# Led_Control.net
KiCad netlist of a schematic drawn in Altium Designer
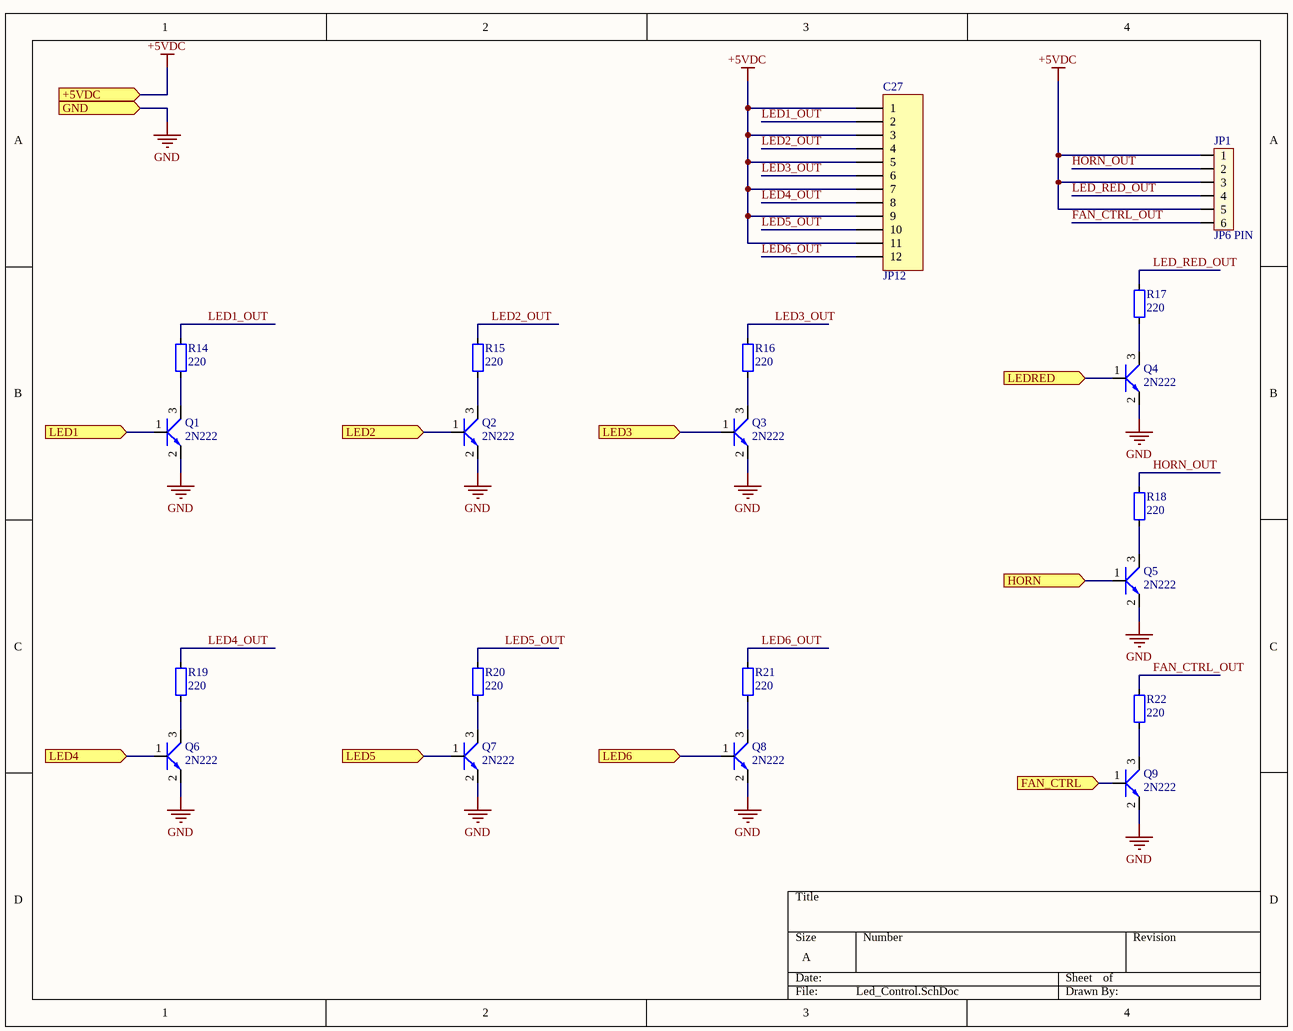
[diagram p0: Led_Control.SchDoc]

(export (version "E")
  (design (tool "Eeschema 10.0.6"))
  (components
    (comp (ref "C27")
      (value "JP12")
      (footprint "JP12-D1T")
      (description "WR-PHD 2.54 mm Angled Socket Header")
      (fields
        (field (name "MANUFACTURER") "Würth Elektronik eiSos GmbH")
        (field (name "PARTNO") "613012143121")
        (field (name "CREATED BY") "Karrer Zheng")
      )
      (libsource (lib "My Library") (part "JP12"))
    )
    (comp (ref "JP1") (value "JP6 PIN") (footprint "JP6") (libsource (lib "My Library") (part "JP6")))
    (comp (ref "Q1")
      (value "2N222")
      (footprint "SOT23D")
      (description "NPN 600mW, ECB")
      (libsource (lib "My Library") (part "2N222"))
    )
    (comp (ref "Q2")
      (value "2N222")
      (footprint "SOT23D")
      (description "NPN 600mW, ECB")
      (libsource (lib "My Library") (part "2N222"))
    )
    (comp (ref "Q3")
      (value "2N222")
      (footprint "SOT23D")
      (description "NPN 600mW, ECB")
      (libsource (lib "My Library") (part "2N222"))
    )
    (comp (ref "Q4")
      (value "2N222")
      (footprint "SOT23D")
      (description "NPN 600mW, ECB")
      (libsource (lib "My Library") (part "2N222"))
    )
    (comp (ref "Q5")
      (value "2N222")
      (footprint "SOT23D")
      (description "NPN 600mW, ECB")
      (libsource (lib "My Library") (part "2N222"))
    )
    (comp (ref "Q6")
      (value "2N222")
      (footprint "SOT23D")
      (description "NPN 600mW, ECB")
      (libsource (lib "My Library") (part "2N222"))
    )
    (comp (ref "Q7")
      (value "2N222")
      (footprint "SOT23D")
      (description "NPN 600mW, ECB")
      (libsource (lib "My Library") (part "2N222"))
    )
    (comp (ref "Q8")
      (value "2N222")
      (footprint "SOT23D")
      (description "NPN 600mW, ECB")
      (libsource (lib "My Library") (part "2N222"))
    )
    (comp (ref "Q9")
      (value "2N222")
      (footprint "SOT23D")
      (description "NPN 600mW, ECB")
      (libsource (lib "My Library") (part "2N222"))
    )
    (comp (ref "R14")
      (value "220")
      (footprint "RES-SMD-0805")
      (description "Resistor")
      (fields
        (field (name "MANUFACTURER") "Generic Components")
        (field (name "PUBLISHER") "Altium Hobart Technology Centre")
      )
      (libsource (lib "My Library") (part "Resistor - SMD"))
    )
    (comp (ref "R15")
      (value "220")
      (footprint "RES-SMD-0805")
      (description "Resistor")
      (fields
        (field (name "MANUFACTURER") "Generic Components")
        (field (name "PUBLISHER") "Altium Hobart Technology Centre")
      )
      (libsource (lib "My Library") (part "Resistor - SMD"))
    )
    (comp (ref "R16")
      (value "220")
      (footprint "RES-SMD-0805")
      (description "Resistor")
      (fields
        (field (name "MANUFACTURER") "Generic Components")
        (field (name "PUBLISHER") "Altium Hobart Technology Centre")
      )
      (libsource (lib "My Library") (part "Resistor - SMD"))
    )
    (comp (ref "R17")
      (value "220")
      (footprint "RES-SMD-0805")
      (description "Resistor")
      (fields
        (field (name "MANUFACTURER") "Generic Components")
        (field (name "PUBLISHER") "Altium Hobart Technology Centre")
      )
      (libsource (lib "My Library") (part "Resistor - SMD"))
    )
    (comp (ref "R18")
      (value "220")
      (footprint "RES-SMD-0805")
      (description "Resistor")
      (fields
        (field (name "MANUFACTURER") "Generic Components")
        (field (name "PUBLISHER") "Altium Hobart Technology Centre")
      )
      (libsource (lib "My Library") (part "Resistor - SMD"))
    )
    (comp (ref "R19")
      (value "220")
      (footprint "RES-SMD-0805")
      (description "Resistor")
      (fields
        (field (name "MANUFACTURER") "Generic Components")
        (field (name "PUBLISHER") "Altium Hobart Technology Centre")
      )
      (libsource (lib "My Library") (part "Resistor - SMD"))
    )
    (comp (ref "R20")
      (value "220")
      (footprint "RES-SMD-0805")
      (description "Resistor")
      (fields
        (field (name "MANUFACTURER") "Generic Components")
        (field (name "PUBLISHER") "Altium Hobart Technology Centre")
      )
      (libsource (lib "My Library") (part "Resistor - SMD"))
    )
    (comp (ref "R21")
      (value "220")
      (footprint "RES-SMD-0805")
      (description "Resistor")
      (fields
        (field (name "MANUFACTURER") "Generic Components")
        (field (name "PUBLISHER") "Altium Hobart Technology Centre")
      )
      (libsource (lib "My Library") (part "Resistor - SMD"))
    )
    (comp (ref "R22")
      (value "220")
      (footprint "RES-SMD-0805")
      (description "Resistor")
      (fields
        (field (name "MANUFACTURER") "Generic Components")
        (field (name "PUBLISHER") "Altium Hobart Technology Centre")
      )
      (libsource (lib "My Library") (part "Resistor - SMD"))
    )
  )
  (nets
    (net (code "1") (name "+5VDC") (class "Default")
      (node (ref "C27") (pin "1") (pinfunction "1_1") (pintype "passive"))
      (node (ref "C27") (pin "11") (pinfunction "11_11") (pintype "passive"))
      (node (ref "C27") (pin "3") (pinfunction "3_3") (pintype "passive"))
      (node (ref "C27") (pin "5") (pinfunction "5_5") (pintype "passive"))
      (node (ref "C27") (pin "7") (pinfunction "7_7") (pintype "passive"))
      (node (ref "C27") (pin "9") (pinfunction "9_9") (pintype "passive"))
      (node (ref "JP1") (pin "1") (pinfunction "1_1") (pintype "passive"))
      (node (ref "JP1") (pin "3") (pinfunction "3_3") (pintype "passive"))
      (node (ref "JP1") (pin "5") (pinfunction "5_5") (pintype "passive"))
    )
    (net (code "2") (name "/FAN_CTRL") (class "Default")
      (node (ref "Q9") (pin "1") (pinfunction "B_1") (pintype "passive"))
    )
    (net (code "3") (name "/FAN_CTRL_OUT") (class "Default")
      (node (ref "JP1") (pin "6") (pinfunction "6_6") (pintype "passive"))
      (node (ref "R22") (pin "2") (pinfunction "2_2") (pintype "passive"))
    )
    (net (code "4") (name "/HORN") (class "Default")
      (node (ref "Q5") (pin "1") (pinfunction "B_1") (pintype "passive"))
    )
    (net (code "5") (name "/HORN_OUT") (class "Default")
      (node (ref "JP1") (pin "2") (pinfunction "2_2") (pintype "passive"))
      (node (ref "R18") (pin "2") (pinfunction "2_2") (pintype "passive"))
    )
    (net (code "6") (name "/LED1") (class "Default")
      (node (ref "Q1") (pin "1") (pinfunction "B_1") (pintype "passive"))
    )
    (net (code "7") (name "/LED1_OUT") (class "Default")
      (node (ref "C27") (pin "2") (pinfunction "2_2") (pintype "passive"))
      (node (ref "R14") (pin "2") (pinfunction "2_2") (pintype "passive"))
    )
    (net (code "8") (name "/LED2") (class "Default")
      (node (ref "Q2") (pin "1") (pinfunction "B_1") (pintype "passive"))
    )
    (net (code "9") (name "/LED2_OUT") (class "Default")
      (node (ref "C27") (pin "4") (pinfunction "4_4") (pintype "passive"))
      (node (ref "R15") (pin "2") (pinfunction "2_2") (pintype "passive"))
    )
    (net (code "10") (name "/LED3") (class "Default")
      (node (ref "Q3") (pin "1") (pinfunction "B_1") (pintype "passive"))
    )
    (net (code "11") (name "/LED3_OUT") (class "Default")
      (node (ref "C27") (pin "6") (pinfunction "6_6") (pintype "passive"))
      (node (ref "R16") (pin "2") (pinfunction "2_2") (pintype "passive"))
    )
    (net (code "12") (name "/LED4") (class "Default")
      (node (ref "Q6") (pin "1") (pinfunction "B_1") (pintype "passive"))
    )
    (net (code "13") (name "/LED4_OUT") (class "Default")
      (node (ref "C27") (pin "8") (pinfunction "8_8") (pintype "passive"))
      (node (ref "R19") (pin "2") (pinfunction "2_2") (pintype "passive"))
    )
    (net (code "14") (name "/LED5") (class "Default")
      (node (ref "Q7") (pin "1") (pinfunction "B_1") (pintype "passive"))
    )
    (net (code "15") (name "/LED5_OUT") (class "Default")
      (node (ref "C27") (pin "10") (pinfunction "10_10") (pintype "passive"))
      (node (ref "R20") (pin "2") (pinfunction "2_2") (pintype "passive"))
    )
    (net (code "16") (name "/LED6") (class "Default")
      (node (ref "Q8") (pin "1") (pinfunction "B_1") (pintype "passive"))
    )
    (net (code "17") (name "/LED6_OUT") (class "Default")
      (node (ref "C27") (pin "12") (pinfunction "12_12") (pintype "passive"))
      (node (ref "R21") (pin "2") (pinfunction "2_2") (pintype "passive"))
    )
    (net (code "18") (name "/LEDRED") (class "Default")
      (node (ref "Q4") (pin "1") (pinfunction "B_1") (pintype "passive"))
    )
    (net (code "19") (name "/LED_RED_OUT") (class "Default")
      (node (ref "JP1") (pin "4") (pinfunction "4_4") (pintype "passive"))
      (node (ref "R17") (pin "2") (pinfunction "2_2") (pintype "passive"))
    )
    (net (code "20") (name "GND") (class "Default")
      (node (ref "Q1") (pin "2") (pinfunction "E_2") (pintype "passive"))
      (node (ref "Q2") (pin "2") (pinfunction "E_2") (pintype "passive"))
      (node (ref "Q3") (pin "2") (pinfunction "E_2") (pintype "passive"))
      (node (ref "Q4") (pin "2") (pinfunction "E_2") (pintype "passive"))
      (node (ref "Q5") (pin "2") (pinfunction "E_2") (pintype "passive"))
      (node (ref "Q6") (pin "2") (pinfunction "E_2") (pintype "passive"))
      (node (ref "Q7") (pin "2") (pinfunction "E_2") (pintype "passive"))
      (node (ref "Q8") (pin "2") (pinfunction "E_2") (pintype "passive"))
      (node (ref "Q9") (pin "2") (pinfunction "E_2") (pintype "passive"))
    )
    (net (code "21") (name "Net-(Q1-C)") (class "Default")
      (node (ref "Q1") (pin "3") (pinfunction "C_3") (pintype "passive"))
      (node (ref "R14") (pin "1") (pinfunction "1_1") (pintype "passive"))
    )
    (net (code "22") (name "Net-(Q2-C)") (class "Default")
      (node (ref "Q2") (pin "3") (pinfunction "C_3") (pintype "passive"))
      (node (ref "R15") (pin "1") (pinfunction "1_1") (pintype "passive"))
    )
    (net (code "23") (name "Net-(Q3-C)") (class "Default")
      (node (ref "Q3") (pin "3") (pinfunction "C_3") (pintype "passive"))
      (node (ref "R16") (pin "1") (pinfunction "1_1") (pintype "passive"))
    )
    (net (code "24") (name "Net-(Q4-C)") (class "Default")
      (node (ref "Q4") (pin "3") (pinfunction "C_3") (pintype "passive"))
      (node (ref "R17") (pin "1") (pinfunction "1_1") (pintype "passive"))
    )
    (net (code "25") (name "Net-(Q5-C)") (class "Default")
      (node (ref "Q5") (pin "3") (pinfunction "C_3") (pintype "passive"))
      (node (ref "R18") (pin "1") (pinfunction "1_1") (pintype "passive"))
    )
    (net (code "26") (name "Net-(Q6-C)") (class "Default")
      (node (ref "Q6") (pin "3") (pinfunction "C_3") (pintype "passive"))
      (node (ref "R19") (pin "1") (pinfunction "1_1") (pintype "passive"))
    )
    (net (code "27") (name "Net-(Q7-C)") (class "Default")
      (node (ref "Q7") (pin "3") (pinfunction "C_3") (pintype "passive"))
      (node (ref "R20") (pin "1") (pinfunction "1_1") (pintype "passive"))
    )
    (net (code "28") (name "Net-(Q8-C)") (class "Default")
      (node (ref "Q8") (pin "3") (pinfunction "C_3") (pintype "passive"))
      (node (ref "R21") (pin "1") (pinfunction "1_1") (pintype "passive"))
    )
    (net (code "29") (name "Net-(Q9-C)") (class "Default")
      (node (ref "Q9") (pin "3") (pinfunction "C_3") (pintype "passive"))
      (node (ref "R22") (pin "1") (pinfunction "1_1") (pintype "passive"))
    )
  )
)
